# I2C_switch.net
KiCad netlist of a schematic drawn in Altium Designer
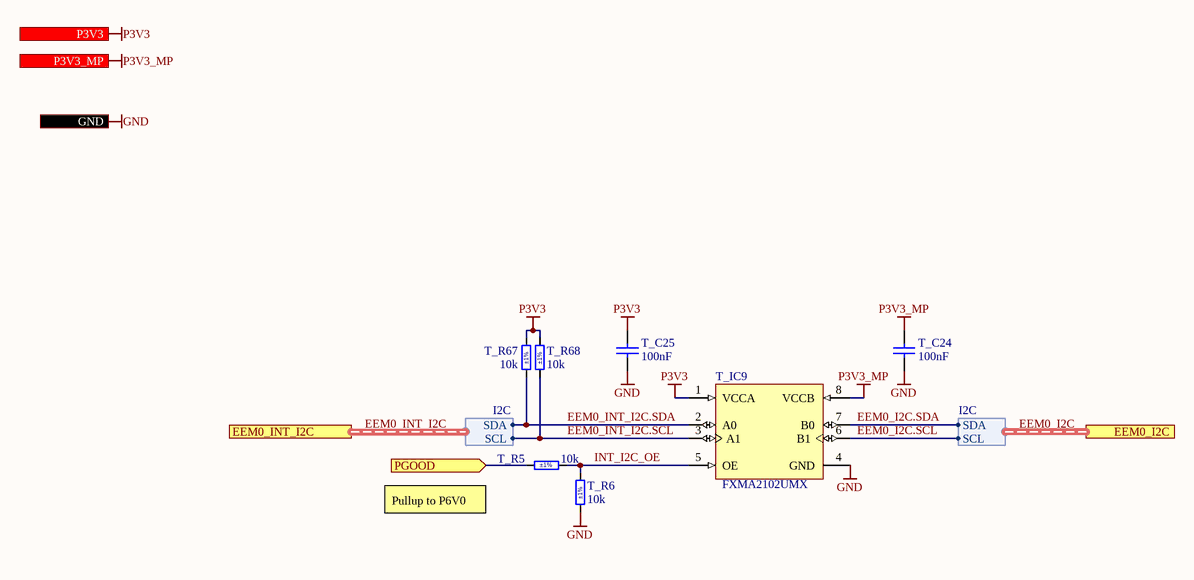
[diagram p0: I2C_switch.SchDoc]

(export (version "E")
  (design (tool "Eeschema 10.0.6"))
  (components
    (comp (ref "T_C24")
      (value "100nF")
      (footprint "CAPC1005X55N")
      (description "Non-polarised capacitor")
      (fields
        (field (name "PART NUMBER") "CC0402_100NF_50V_10%_X7R")
        (field (name "VOLTAGE") "50V")
        (field (name "AUTHOR") "CERN DEM MR")
      )
      (libsource (lib "Capacitors") (part "Capacitor - non polarized"))
    )
    (comp (ref "T_C25")
      (value "100nF")
      (footprint "CAPC1005X55N")
      (description "Non-polarised capacitor")
      (fields
        (field (name "PART NUMBER") "CC0402_100NF_50V_10%_X7R")
        (field (name "VOLTAGE") "50V")
        (field (name "AUTHOR") "CERN DEM MR")
      )
      (libsource (lib "Capacitors") (part "Capacitor - non polarized"))
    )
    (comp (ref "T_IC9")
      (value "FXMA2102UMX")
      (footprint "FXMA2102UMX")
      (description "Dual Supply 2-Bit Voltage Translator/Buffer/Repeater Isolator for I2C Applications")
      (fields (field (name "MANUFACTURER") "Onsemi"))
      (libsource (lib "TechnoSystem Workspace") (part "FXMA2102UMX"))
    )
    (comp (ref "T_R5")
      (value "10k")
      (footprint "RESC1005X40N")
      (description "Resistor - 1%")
      (fields
        (field (name "TOLERANCE") "±1%")
        (field (name "PART NUMBER") "R0402_10K_1%_0.0625W_100PPM")
        (field (name "POWER") "0.0625W")
        (field (name "AUTHOR") "CERN DEM JLC")
      )
      (libsource (lib "Resistors") (part "Resistor - 1%"))
    )
    (comp (ref "T_R6")
      (value "10k")
      (footprint "RESC1005X40N")
      (description "Resistor - 1%")
      (fields
        (field (name "TOLERANCE") "±1%")
        (field (name "PART NUMBER") "R0402_10K_1%_0.0625W_100PPM")
        (field (name "POWER") "0.0625W")
        (field (name "AUTHOR") "CERN DEM JLC")
      )
      (libsource (lib "Resistors") (part "Resistor - 1%"))
    )
    (comp (ref "T_R67")
      (value "10k")
      (footprint "RESC1005X40N")
      (description "Resistor - 1%")
      (fields
        (field (name "TOLERANCE") "±1%")
        (field (name "PART NUMBER") "R0402_10K_1%_0.0625W_100PPM")
        (field (name "POWER") "0.0625W")
        (field (name "AUTHOR") "CERN DEM JLC")
      )
      (libsource (lib "Resistors") (part "Resistor - 1%"))
    )
    (comp (ref "T_R68")
      (value "10k")
      (footprint "RESC1005X40N")
      (description "Resistor - 1%")
      (fields
        (field (name "TOLERANCE") "±1%")
        (field (name "PART NUMBER") "R0402_10K_1%_0.0625W_100PPM")
        (field (name "POWER") "0.0625W")
        (field (name "AUTHOR") "CERN DEM JLC")
      )
      (libsource (lib "Resistors") (part "Resistor - 1%"))
    )
  )
  (nets
    (net (code "3") (name "/EEM0_I2C.SCL") (class "Default")
      (node (ref "T_IC9") (pin "6") (pinfunction "B1_6") (pintype "bidirectional"))
    )
    (net (code "4") (name "/EEM0_I2C.SDA") (class "Default")
      (node (ref "T_IC9") (pin "7") (pinfunction "B0_7") (pintype "bidirectional"))
    )
    (net (code "6") (name "/EEM0_INT_I2C.SCL") (class "Default")
      (node (ref "T_IC9") (pin "3") (pinfunction "A1_3") (pintype "bidirectional"))
      (node (ref "T_R68") (pin "1") (pinfunction "1_1") (pintype "passive"))
    )
    (net (code "7") (name "/EEM0_INT_I2C.SDA") (class "Default")
      (node (ref "T_IC9") (pin "2") (pinfunction "A0_2") (pintype "bidirectional"))
      (node (ref "T_R67") (pin "1") (pinfunction "1_1") (pintype "passive"))
    )
    (net (code "9") (name "/INT_I2C_OE") (class "Default")
      (node (ref "T_IC9") (pin "5") (pinfunction "OE_5") (pintype "input"))
      (node (ref "T_R5") (pin "2") (pinfunction "2_2") (pintype "passive"))
      (node (ref "T_R6") (pin "2") (pinfunction "2_2") (pintype "passive"))
    )
    (net (code "10") (name "/PGOOD") (class "Default")
      (node (ref "T_R5") (pin "1") (pinfunction "1_1") (pintype "passive"))
    )
    (net (code "11") (name "GND") (class "Default")
      (node (ref "T_C24") (pin "1") (pinfunction "1_1") (pintype "passive"))
      (node (ref "T_C25") (pin "1") (pinfunction "1_1") (pintype "passive"))
      (node (ref "T_IC9") (pin "4") (pinfunction "GND_4") (pintype "power_in"))
      (node (ref "T_R6") (pin "1") (pinfunction "1_1") (pintype "passive"))
    )
    (net (code "12") (name "P3V3") (class "Default")
      (node (ref "T_C25") (pin "2") (pinfunction "2_2") (pintype "passive"))
      (node (ref "T_IC9") (pin "1") (pinfunction "VCCA_1") (pintype "input"))
      (node (ref "T_R67") (pin "2") (pinfunction "2_2") (pintype "passive"))
      (node (ref "T_R68") (pin "2") (pinfunction "2_2") (pintype "passive"))
    )
    (net (code "13") (name "P3V3_MP") (class "Default")
      (node (ref "T_C24") (pin "2") (pinfunction "2_2") (pintype "passive"))
      (node (ref "T_IC9") (pin "8") (pinfunction "VCCB_8") (pintype "input"))
    )
  )
)
